# schematic.net
KiCad netlist of a schematic drawn in EasyEDA
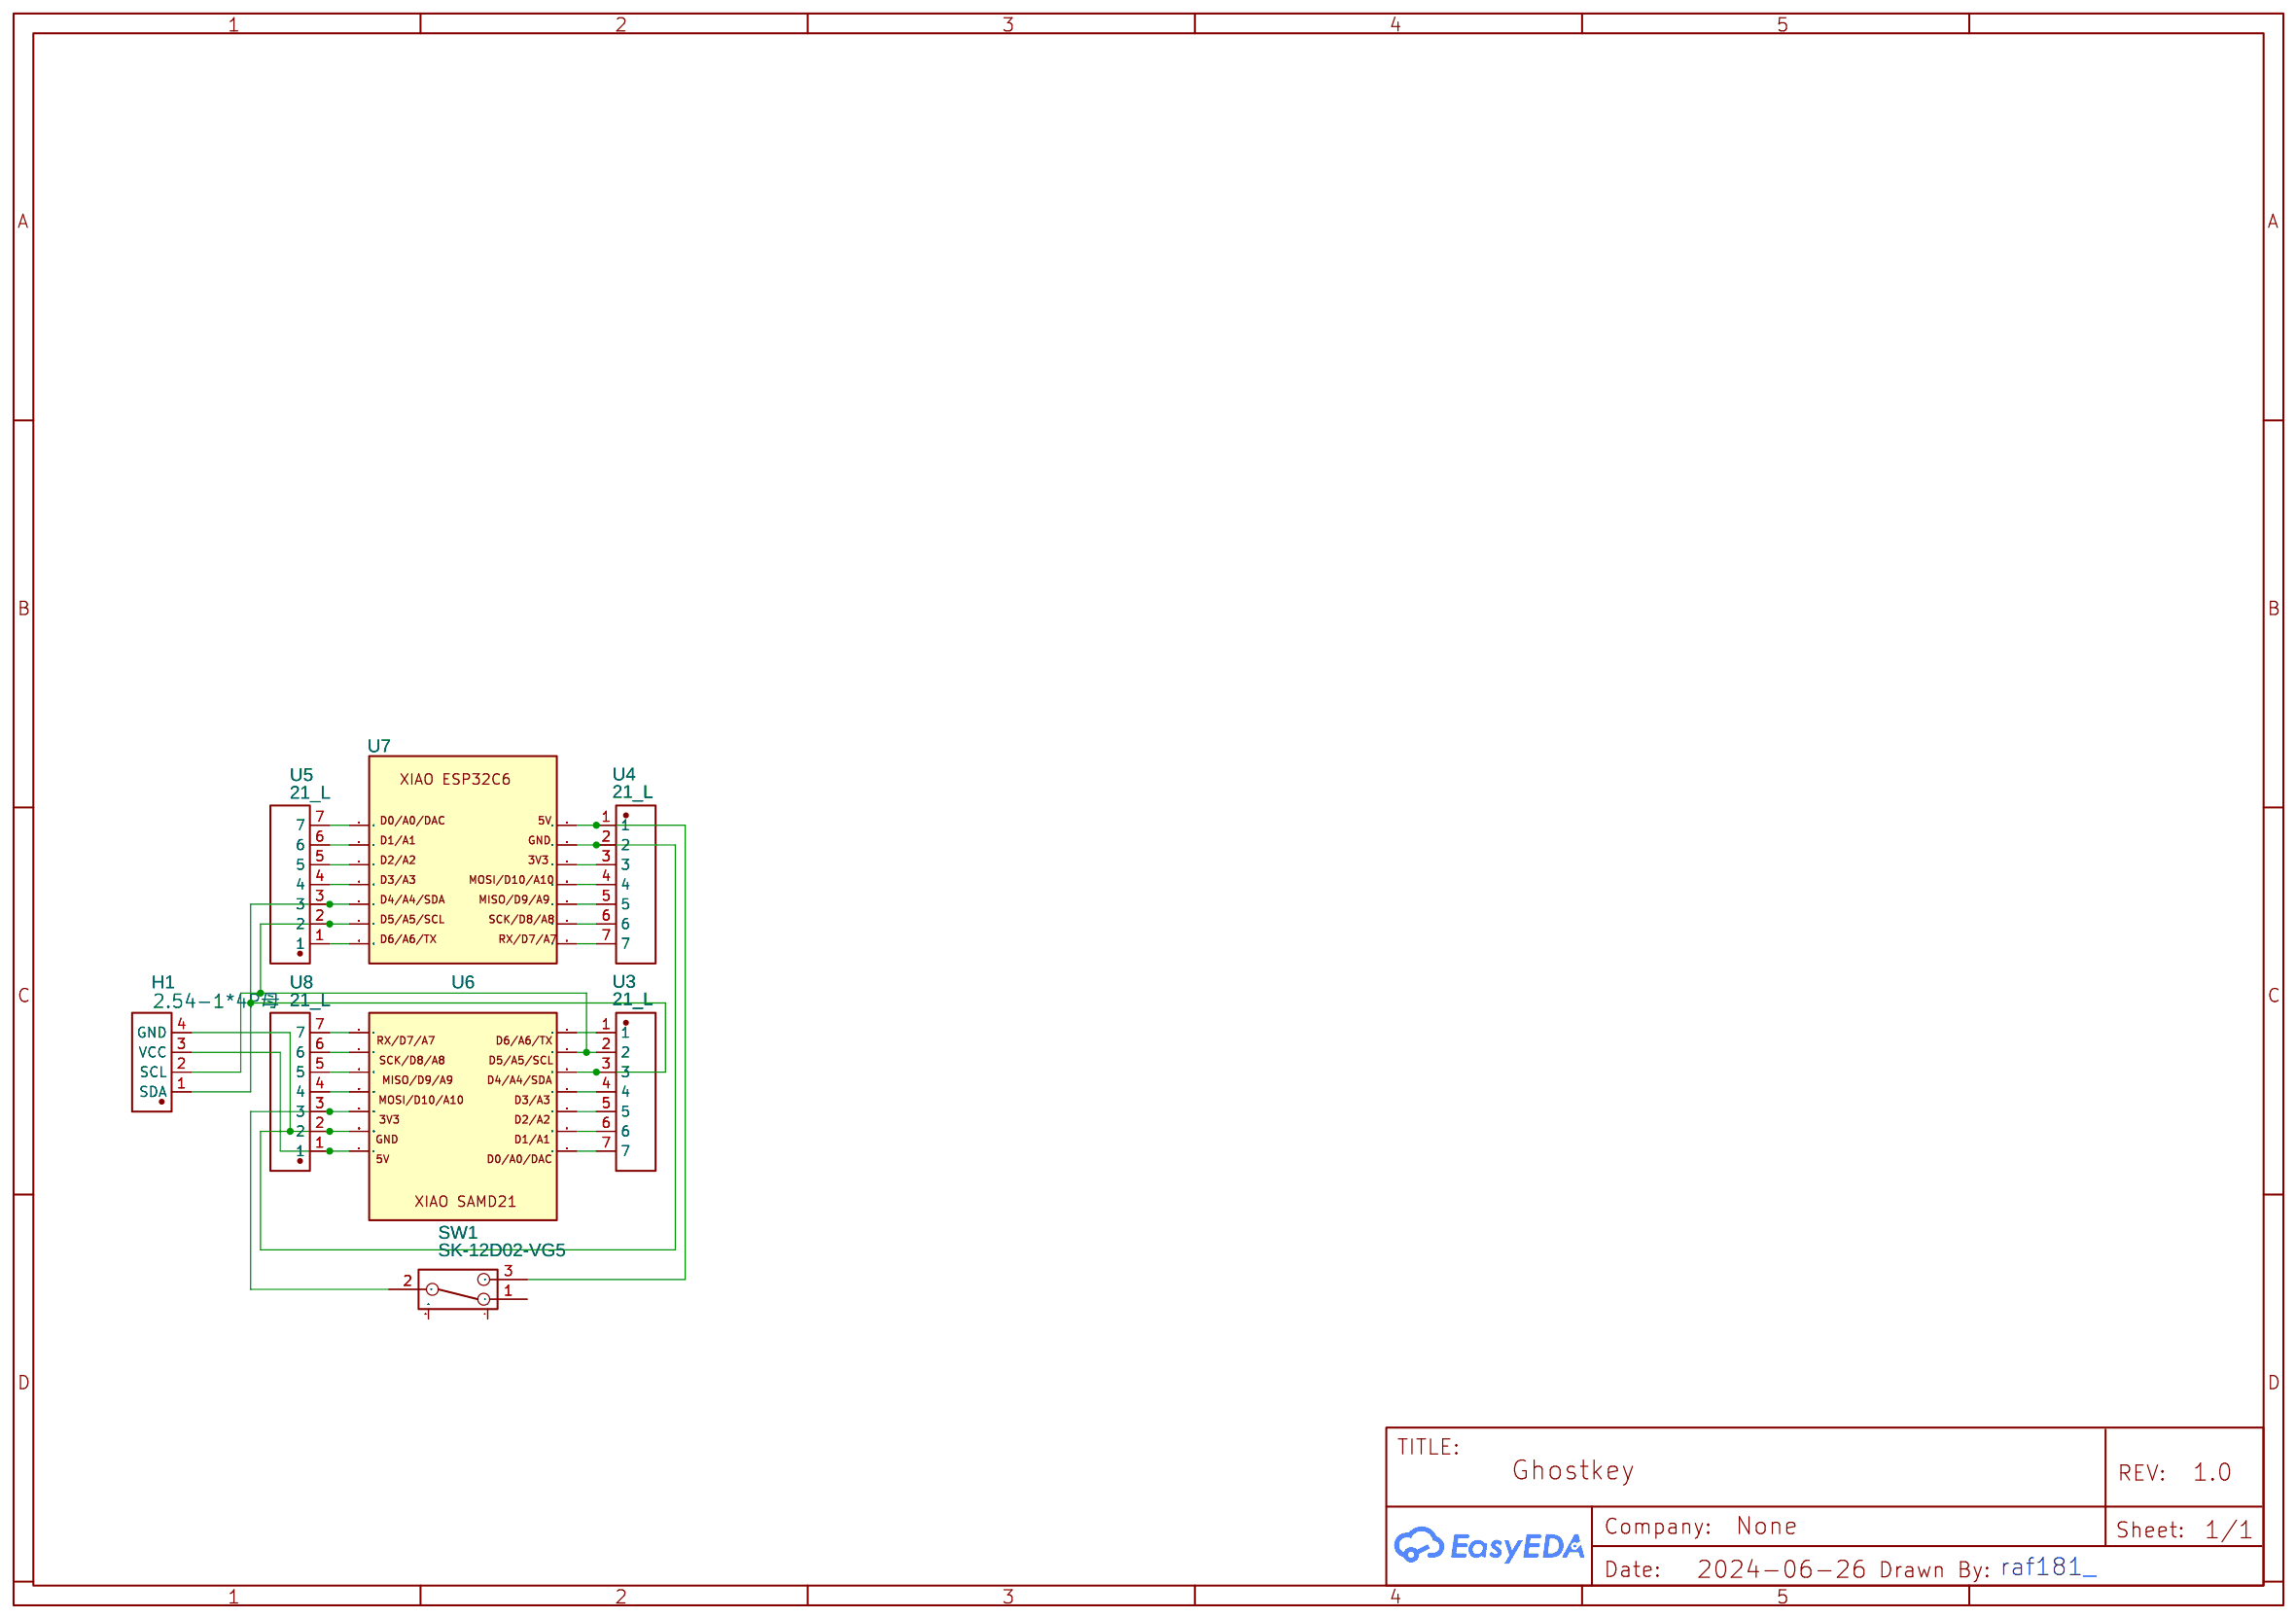
[diagram p0: schematic sheet]

(export (version "E")
  (design (tool "Eeschema 10.0.6"))
  (components
    (comp (ref "H1")
      (value "2.54-1*4P母")
      (fields (field (name "Manufacturer") "BOOMELE(博穆精密)"))
      (libsource (lib "") (part "2.54-1*4P母"))
    )
    (comp (ref "SW1")
      (value "SK-12D02-VG5")
      (fields (field (name "Manufacturer") "韩国韩荣"))
      (libsource (lib "") (part "SK-12D02-VG5"))
    )
    (comp (ref "U3")
      (value "21_L")
      (fields
        (field (name "Manufacturer Part") "HB-PH3-25417PB2GOP")
        (field (name "Manufacturer") "HANBO(汉博)")
      )
      (libsource (lib "") (part "HB-PH3-25417PB2GOP"))
    )
    (comp (ref "U4")
      (value "21_L")
      (fields
        (field (name "Manufacturer Part") "HB-PH3-25417PB2GOP")
        (field (name "Manufacturer") "HANBO(汉博)")
      )
      (libsource (lib "") (part "HB-PH3-25417PB2GOP"))
    )
    (comp (ref "U5")
      (value "21_L")
      (fields
        (field (name "Manufacturer Part") "HB-PH3-25417PB2GOP")
        (field (name "Manufacturer") "HANBO(汉博)")
      )
      (libsource (lib "") (part "HB-PH3-25417PB2GOP_1"))
    )
    (comp (ref "U6")
      (value "SEEEDUINO  XIAO")
      (fields (field (name "Manufacturer Part") "102010328") (field (name "Manufacturer") "Seeed Studio"))
      (libsource (lib "") (part "SEEEDUINO  XIAO_1"))
    )
    (comp (ref "U7")
      (value "SEEEDUINO  XIAO")
      (fields (field (name "Manufacturer Part") "102010328") (field (name "Manufacturer") "Seeed Studio"))
      (libsource (lib "") (part "SEEEDUINO  XIAO"))
    )
    (comp (ref "U8")
      (value "21_L")
      (fields
        (field (name "Manufacturer Part") "HB-PH3-25417PB2GOP")
        (field (name "Manufacturer") "HANBO(汉博)")
      )
      (libsource (lib "") (part "HB-PH3-25417PB2GOP_1"))
    )
  )
  (nets
    (net (code "1") (name "Net-(H1-GND)") (class "Default")
      (node (ref "H1") (pin "4") (pinfunction "GND_4") (pintype "unspecified"))
      (node (ref "U4") (pin "2") (pinfunction "2_2") (pintype "unspecified"))
      (node (ref "U6") (pin "GND") (pinfunction "GND_GND") (pintype "bidirectional"))
      (node (ref "U7") (pin "GND") (pinfunction "GND_GND") (pintype "bidirectional"))
      (node (ref "U8") (pin "2") (pinfunction "2_2") (pintype "unspecified"))
    )
    (net (code "2") (name "Net-(H1-SCL)") (class "Default")
      (node (ref "H1") (pin "2") (pinfunction "SCL_2") (pintype "unspecified"))
      (node (ref "U3") (pin "2") (pinfunction "2_2") (pintype "unspecified"))
      (node (ref "U5") (pin "2") (pinfunction "2_2") (pintype "unspecified"))
      (node (ref "U6") (pin "D5") (pinfunction "D5_D5") (pintype "bidirectional"))
      (node (ref "U7") (pin "D5") (pinfunction "D5_D5") (pintype "bidirectional"))
    )
    (net (code "3") (name "Net-(H1-SDA)") (class "Default")
      (node (ref "H1") (pin "1") (pinfunction "SDA_1") (pintype "unspecified"))
      (node (ref "U3") (pin "3") (pinfunction "3_3") (pintype "unspecified"))
      (node (ref "U5") (pin "3") (pinfunction "3_3") (pintype "unspecified"))
      (node (ref "U6") (pin "D4") (pinfunction "D4_D4") (pintype "bidirectional"))
      (node (ref "U7") (pin "D4") (pinfunction "D4_D4") (pintype "bidirectional"))
    )
    (net (code "4") (name "Net-(H1-VCC)") (class "Default")
      (node (ref "H1") (pin "3") (pinfunction "VCC_3") (pintype "unspecified"))
      (node (ref "U6") (pin "5V") (pinfunction "5V_5V") (pintype "bidirectional"))
      (node (ref "U8") (pin "1") (pinfunction "1_1") (pintype "unspecified"))
    )
    (net (code "5") (name "Net-(SW1-Pad2)") (class "Default")
      (node (ref "SW1") (pin "2") (pinfunction "2_2") (pintype "unspecified"))
      (node (ref "U6") (pin "3V3") (pinfunction "3V3_3V3") (pintype "bidirectional"))
      (node (ref "U8") (pin "3") (pinfunction "3_3") (pintype "unspecified"))
    )
    (net (code "6") (name "Net-(SW1-Pad3)") (class "Default")
      (node (ref "SW1") (pin "3") (pinfunction "3_3") (pintype "unspecified"))
      (node (ref "U4") (pin "1") (pinfunction "1_1") (pintype "unspecified"))
      (node (ref "U7") (pin "5V") (pinfunction "5V_5V") (pintype "bidirectional"))
    )
    (net (code "7") (name "Net-(U3-Pad1)") (class "Default")
      (node (ref "U3") (pin "1") (pinfunction "1_1") (pintype "unspecified"))
      (node (ref "U6") (pin "D6") (pinfunction "D6_D6") (pintype "bidirectional"))
    )
    (net (code "8") (name "Net-(U3-Pad4)") (class "Default")
      (node (ref "U3") (pin "4") (pinfunction "4_4") (pintype "unspecified"))
      (node (ref "U6") (pin "D3") (pinfunction "D3_D3") (pintype "bidirectional"))
    )
    (net (code "9") (name "Net-(U3-Pad5)") (class "Default")
      (node (ref "U3") (pin "5") (pinfunction "5_5") (pintype "unspecified"))
      (node (ref "U6") (pin "D2") (pinfunction "D2_D2") (pintype "bidirectional"))
    )
    (net (code "10") (name "Net-(U3-Pad6)") (class "Default")
      (node (ref "U3") (pin "6") (pinfunction "6_6") (pintype "unspecified"))
      (node (ref "U6") (pin "D1") (pinfunction "D1_D1") (pintype "bidirectional"))
    )
    (net (code "11") (name "Net-(U3-Pad7)") (class "Default")
      (node (ref "U3") (pin "7") (pinfunction "7_7") (pintype "unspecified"))
      (node (ref "U6") (pin "D0") (pinfunction "D0_D0") (pintype "bidirectional"))
    )
    (net (code "12") (name "Net-(U4-Pad3)") (class "Default")
      (node (ref "U4") (pin "3") (pinfunction "3_3") (pintype "unspecified"))
      (node (ref "U7") (pin "3V3") (pinfunction "3V3_3V3") (pintype "bidirectional"))
    )
    (net (code "13") (name "Net-(U4-Pad4)") (class "Default")
      (node (ref "U4") (pin "4") (pinfunction "4_4") (pintype "unspecified"))
      (node (ref "U7") (pin "D10") (pinfunction "D10_D10") (pintype "bidirectional"))
    )
    (net (code "14") (name "Net-(U4-Pad5)") (class "Default")
      (node (ref "U4") (pin "5") (pinfunction "5_5") (pintype "unspecified"))
      (node (ref "U7") (pin "D9") (pinfunction "D9_D9") (pintype "bidirectional"))
    )
    (net (code "15") (name "Net-(U4-Pad6)") (class "Default")
      (node (ref "U4") (pin "6") (pinfunction "6_6") (pintype "unspecified"))
      (node (ref "U7") (pin "D8") (pinfunction "D8_D8") (pintype "bidirectional"))
    )
    (net (code "16") (name "Net-(U4-Pad7)") (class "Default")
      (node (ref "U4") (pin "7") (pinfunction "7_7") (pintype "unspecified"))
      (node (ref "U7") (pin "D7") (pinfunction "D7_D7") (pintype "bidirectional"))
    )
    (net (code "17") (name "Net-(U5-Pad1)") (class "Default")
      (node (ref "U5") (pin "1") (pinfunction "1_1") (pintype "unspecified"))
      (node (ref "U7") (pin "D6") (pinfunction "D6_D6") (pintype "bidirectional"))
    )
    (net (code "18") (name "Net-(U5-Pad4)") (class "Default")
      (node (ref "U5") (pin "4") (pinfunction "4_4") (pintype "unspecified"))
      (node (ref "U7") (pin "D3") (pinfunction "D3_D3") (pintype "bidirectional"))
    )
    (net (code "19") (name "Net-(U5-Pad5)") (class "Default")
      (node (ref "U5") (pin "5") (pinfunction "5_5") (pintype "unspecified"))
      (node (ref "U7") (pin "D2") (pinfunction "D2_D2") (pintype "bidirectional"))
    )
    (net (code "20") (name "Net-(U5-Pad6)") (class "Default")
      (node (ref "U5") (pin "6") (pinfunction "6_6") (pintype "unspecified"))
      (node (ref "U7") (pin "D1") (pinfunction "D1_D1") (pintype "bidirectional"))
    )
    (net (code "21") (name "Net-(U5-Pad7)") (class "Default")
      (node (ref "U5") (pin "7") (pinfunction "7_7") (pintype "unspecified"))
      (node (ref "U7") (pin "D0") (pinfunction "D0_D0") (pintype "bidirectional"))
    )
    (net (code "22") (name "Net-(U6-PadD7)") (class "Default")
      (node (ref "U6") (pin "D7") (pinfunction "D7_D7") (pintype "bidirectional"))
      (node (ref "U8") (pin "7") (pinfunction "7_7") (pintype "unspecified"))
    )
    (net (code "23") (name "Net-(U6-PadD8)") (class "Default")
      (node (ref "U6") (pin "D8") (pinfunction "D8_D8") (pintype "bidirectional"))
      (node (ref "U8") (pin "6") (pinfunction "6_6") (pintype "unspecified"))
    )
    (net (code "24") (name "Net-(U6-PadD9)") (class "Default")
      (node (ref "U6") (pin "D9") (pinfunction "D9_D9") (pintype "bidirectional"))
      (node (ref "U8") (pin "5") (pinfunction "5_5") (pintype "unspecified"))
    )
    (net (code "25") (name "Net-(U6-PadD10)") (class "Default")
      (node (ref "U6") (pin "D10") (pinfunction "D10_D10") (pintype "bidirectional"))
      (node (ref "U8") (pin "4") (pinfunction "4_4") (pintype "unspecified"))
    )
    (net (code "26") (name "unconnected-(SW1-Pad1)") (class "Default")
      (node (ref "SW1") (pin "1") (pinfunction "1_1") (pintype "unspecified"))
    )
    (net (code "27") (name "unconnected-(SW1-Pad4)") (class "Default")
      (node (ref "SW1") (pin "4") (pinfunction "4_4") (pintype "unspecified"))
    )
    (net (code "28") (name "unconnected-(SW1-Pad5)") (class "Default")
      (node (ref "SW1") (pin "5") (pinfunction "5_5") (pintype "unspecified"))
    )
  )
)
